# Power_Supply.net
KiCad netlist of a schematic drawn in Altium Designer
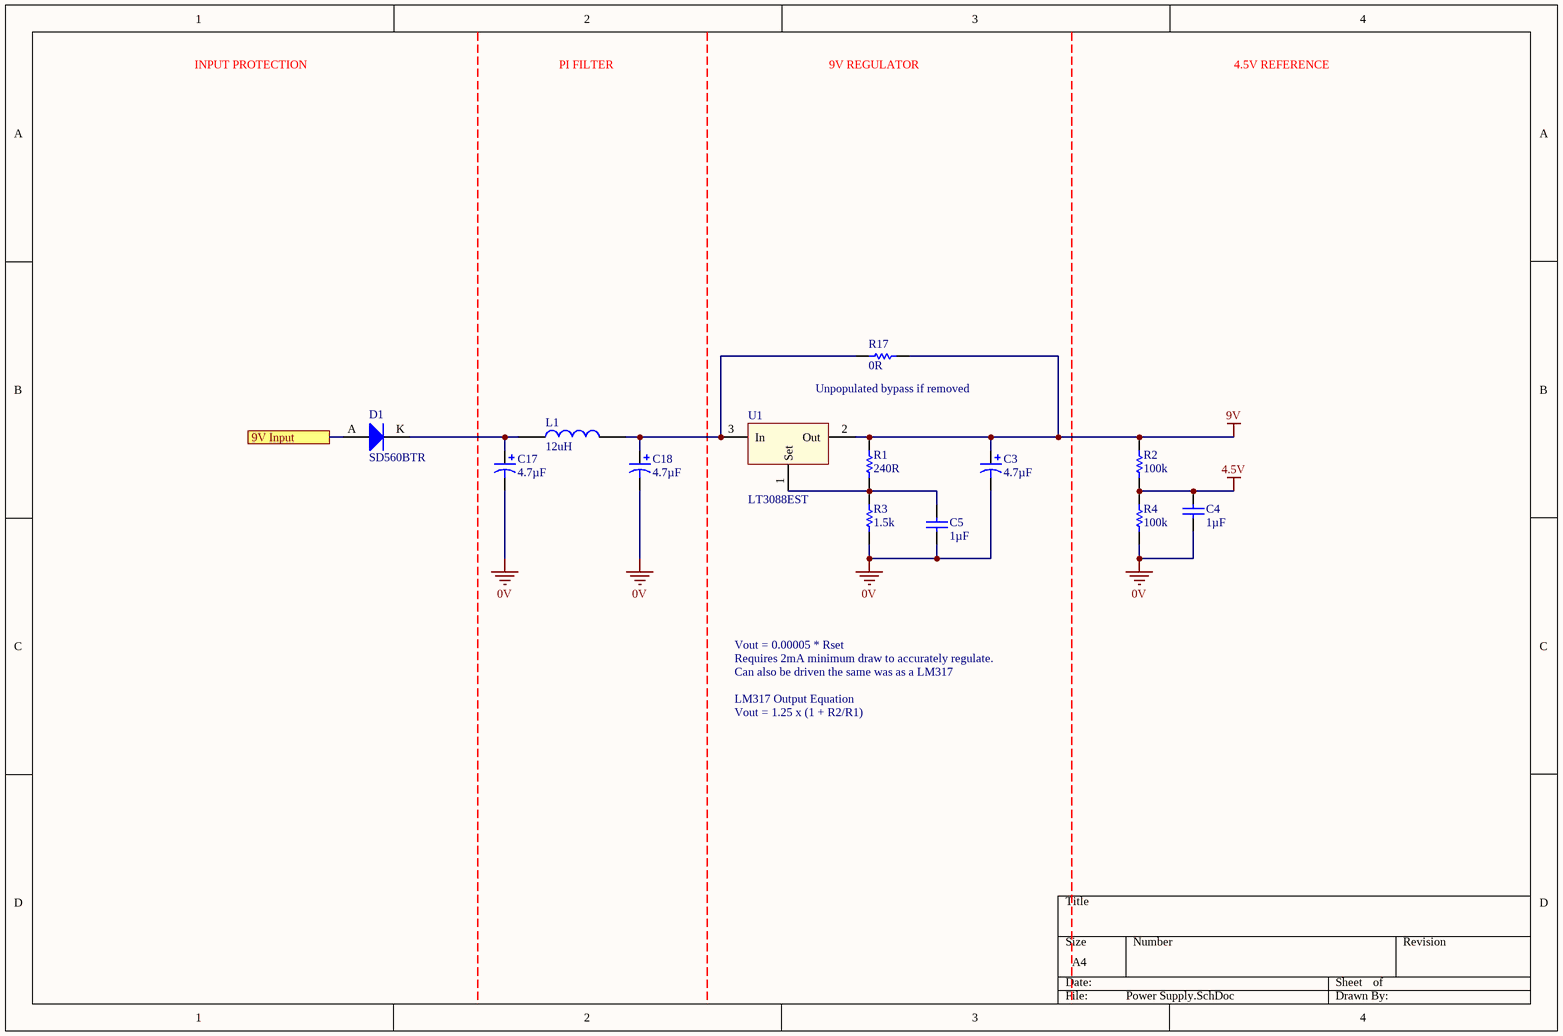
[diagram p0: Power Supply.SchDoc]

(export (version "E")
  (design (tool "Eeschema 10.0.6"))
  (components
    (comp (ref "C3")
      (value "~")
      (footprint "1206")
      (fields
        (field (name "PART NUMBER") "TAJA475K025RNJ")
        (field (name "TOLERANCE") "±10%")
        (field (name "MANUFACTURER") "AVX Corporation")
      )
      (libsource (lib "ts_20-standard-library") (part "Capacitor (Polarised)"))
    )
    (comp (ref "C4")
      (value "1µF")
      (footprint "0805")
      (fields
        (field (name "PART NUMBER") "GCM21BR71H105KA03L")
        (field (name "TOLERANCE") "±10%")
        (field (name "MANUFACTURER") "muRata")
      )
      (libsource (lib "ts_20-standard-library") (part "Capacitor"))
    )
    (comp (ref "C5")
      (value "1µF")
      (footprint "0805")
      (fields
        (field (name "PART NUMBER") "GCM21BR71H105KA03L")
        (field (name "TOLERANCE") "±10%")
        (field (name "MANUFACTURER") "muRata")
      )
      (libsource (lib "ts_20-standard-library") (part "Capacitor"))
    )
    (comp (ref "C17")
      (value "~")
      (footprint "1206")
      (fields
        (field (name "PART NUMBER") "TAJA475K025RNJ")
        (field (name "TOLERANCE") "±10%")
        (field (name "MANUFACTURER") "AVX Corporation")
      )
      (libsource (lib "ts_20-standard-library") (part "Capacitor (Polarised)"))
    )
    (comp (ref "C18")
      (value "~")
      (footprint "1206")
      (fields
        (field (name "PART NUMBER") "TAJA475K025RNJ")
        (field (name "TOLERANCE") "±10%")
        (field (name "MANUFACTURER") "AVX Corporation")
      )
      (libsource (lib "ts_20-standard-library") (part "Capacitor (Polarised)"))
    )
    (comp (ref "D1")
      (value "SD560BTR")
      (footprint "SMB Diode")
      (description "1.2V_F 600V 5A SMB")
      (fields
        (field (name "MANUFACTURER") "SMC Diode Solutions")
        (field (name "DIGIKEY PART NUMBER") "1655-1530-2-ND")
      )
      (libsource (lib "ts_20-standard-library") (part "Diode"))
    )
    (comp (ref "L1")
      (value "12uH")
      (footprint "1812")
      (fields
        (field (name "PART NUMBER") "RLS-126")
        (field (name "MANUFACTURER") "Recom")
        (field (name "TOLERANCE") "0.2")
      )
      (libsource (lib "ts_20-standard-library") (part "Inductor"))
    )
    (comp (ref "R1")
      (value "240R")
      (footprint "0805")
      (fields
        (field (name "PART NUMBER") "RC0805FR07240RL")
        (field (name "MANUFACTURER") "YAGEO")
        (field (name "TOLERANCE") "0.01")
      )
      (libsource (lib "ts_20-standard-library") (part "Resistor"))
    )
    (comp (ref "R2")
      (value "100k")
      (footprint "0805")
      (fields
        (field (name "PART NUMBER") "RC0805FR07100KL")
        (field (name "MANUFACTURER") "YAGEO")
        (field (name "TOLERANCE") "0.01")
      )
      (libsource (lib "ts_20-standard-library") (part "Resistor"))
    )
    (comp (ref "R3")
      (value "1.5k")
      (footprint "0805")
      (fields
        (field (name "PART NUMBER") "RC0805FR071K5L")
        (field (name "MANUFACTURER") "YAGEO")
        (field (name "TOLERANCE") "0.01")
      )
      (libsource (lib "ts_20-standard-library") (part "Resistor"))
    )
    (comp (ref "R4")
      (value "100k")
      (footprint "0805")
      (fields
        (field (name "PART NUMBER") "RC0805FR07100KL")
        (field (name "MANUFACTURER") "YAGEO")
        (field (name "TOLERANCE") "0.01")
      )
      (libsource (lib "ts_20-standard-library") (part "Resistor"))
    )
    (comp (ref "R17")
      (value "0R")
      (footprint "0805")
      (fields
        (field (name "PART NUMBER") "RC0805FR070RL")
        (field (name "MANUFACTURER") "YAGEO")
        (field (name "TOLERANCE") "0.01")
      )
      (libsource (lib "ts_20-standard-library") (part "Resistor"))
    )
    (comp (ref "U1")
      (value "LT3088EST")
      (footprint "LT SOT-223")
      (description "Linear Voltage Regulator IC Output 800mA SOT-223-3")
      (fields
        (field (name "MANUFACTURER") "Linear Technologies")
        (field (name "DIGIKEY PART NUMBER") "LT3088EST#PBF-ND")
      )
      (libsource (lib "ts_20-standard-library") (part "LT3088EST"))
    )
  )
  (nets
    (net (code "1") (name "/9V Input") (class "Default")
      (node (ref "D1") (pin "A") (pinfunction "A_A") (pintype "passive"))
    )
    (net (code "2") (name "0V") (class "Default")
      (node (ref "C17") (pin "1") (pinfunction "1_1") (pintype "passive"))
      (node (ref "C18") (pin "1") (pinfunction "1_1") (pintype "passive"))
      (node (ref "C3") (pin "1") (pinfunction "1_1") (pintype "passive"))
      (node (ref "C4") (pin "1") (pinfunction "1_1") (pintype "passive"))
      (node (ref "C5") (pin "1") (pinfunction "1_1") (pintype "passive"))
      (node (ref "R3") (pin "1") (pinfunction "1_1") (pintype "passive"))
      (node (ref "R4") (pin "1") (pinfunction "1_1") (pintype "passive"))
    )
    (net (code "3") (name "4.5V") (class "Default")
      (node (ref "C4") (pin "2") (pinfunction "2_2") (pintype "passive"))
      (node (ref "R2") (pin "1") (pinfunction "1_1") (pintype "passive"))
      (node (ref "R4") (pin "2") (pinfunction "2_2") (pintype "passive"))
    )
    (net (code "4") (name "9V") (class "Default")
      (node (ref "C3") (pin "2") (pinfunction "2_2") (pintype "passive"))
      (node (ref "R1") (pin "2") (pinfunction "2_2") (pintype "passive"))
      (node (ref "R17") (pin "2") (pinfunction "2_2") (pintype "passive"))
      (node (ref "R2") (pin "2") (pinfunction "2_2") (pintype "passive"))
      (node (ref "U1") (pin "2") (pinfunction "Out_2") (pintype "passive"))
    )
    (net (code "5") (name "Net-(C17-Pad2)") (class "Default")
      (node (ref "C17") (pin "2") (pinfunction "2_2") (pintype "passive"))
      (node (ref "D1") (pin "K") (pinfunction "K_K") (pintype "passive"))
      (node (ref "L1") (pin "2") (pinfunction "2_2") (pintype "passive"))
    )
    (net (code "6") (name "Net-(U1-In)") (class "Default")
      (node (ref "C18") (pin "2") (pinfunction "2_2") (pintype "passive"))
      (node (ref "L1") (pin "1") (pinfunction "1_1") (pintype "passive"))
      (node (ref "R17") (pin "1") (pinfunction "1_1") (pintype "passive"))
      (node (ref "U1") (pin "3") (pinfunction "In_3") (pintype "passive"))
    )
    (net (code "7") (name "Net-(U1-Set)") (class "Default")
      (node (ref "C5") (pin "2") (pinfunction "2_2") (pintype "passive"))
      (node (ref "R1") (pin "1") (pinfunction "1_1") (pintype "passive"))
      (node (ref "R3") (pin "2") (pinfunction "2_2") (pintype "passive"))
      (node (ref "U1") (pin "1") (pinfunction "Set_1") (pintype "passive"))
    )
  )
)
